# high_start.net
KiCad netlist of a schematic drawn in EAGLE
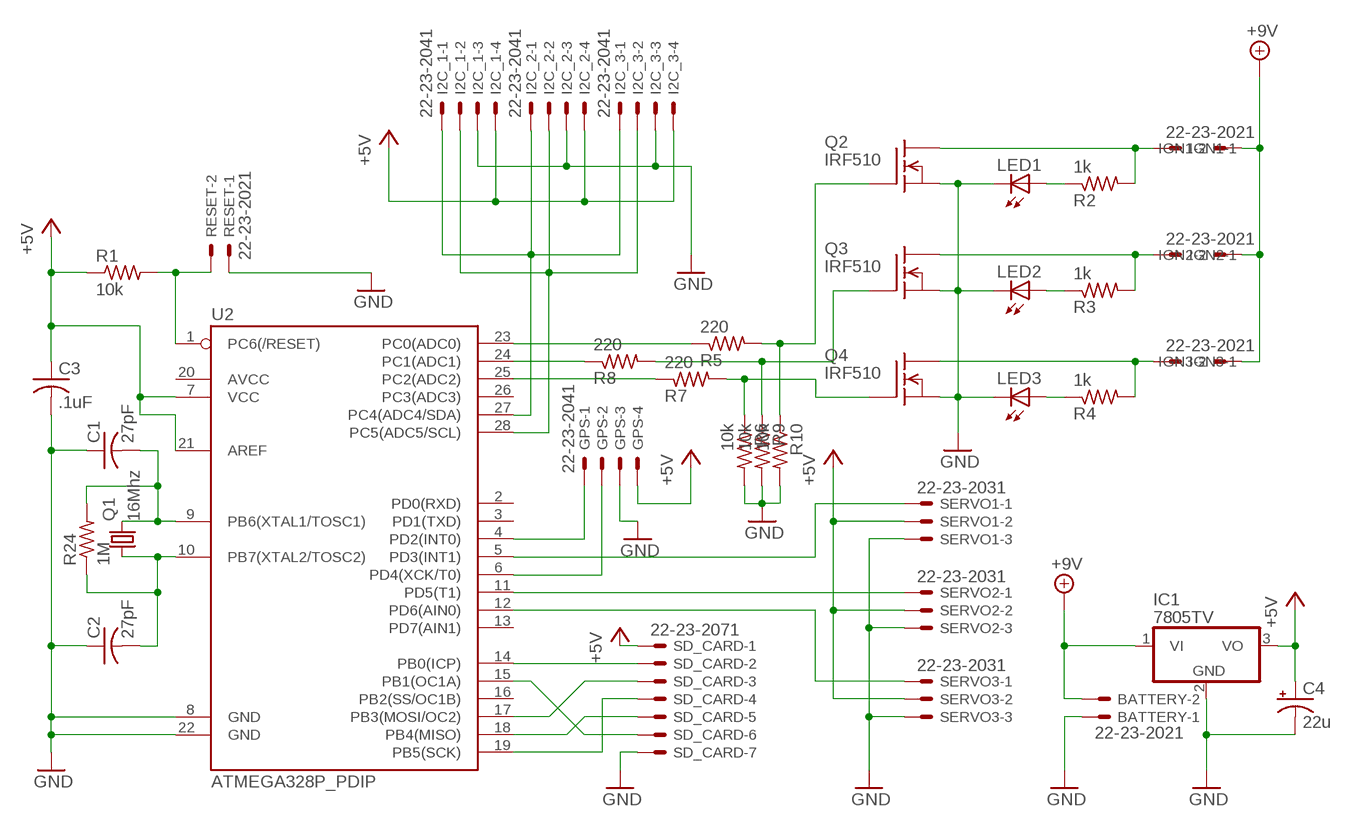
[diagram p0: schematic, sheet 1]

(export (version "E")
  (design (tool "Eeschema 10.0.6"))
  (components
    (comp (ref "BATTERY")
      (value "22-23-2021")
      (footprint "eagle-import:22-23-2021")
      (fields (field (name "MF") "MOLEX"))
      (libsource (lib "eagle-import") (part "22-23-2021"))
    )
    (comp (ref "C1")
      (value "27pF")
      (footprint "eagle-import:C025-040X050")
      (libsource (lib "eagle-import") (part "C-US025-040X050"))
    )
    (comp (ref "C2")
      (value "27pF")
      (footprint "eagle-import:C025-040X050")
      (libsource (lib "eagle-import") (part "C-US025-040X050"))
    )
    (comp (ref "C3")
      (value ".1uF")
      (footprint "eagle-import:C025-030X050")
      (libsource (lib "eagle-import") (part "C-US025-030X050"))
    )
    (comp (ref "C4")
      (value "22u")
      (footprint "eagle-import:B45181A")
      (libsource (lib "eagle-import") (part "CPOL-USB45181A"))
    )
    (comp (ref "GPS")
      (value "22-23-2041")
      (footprint "eagle-import:22-23-2041")
      (fields (field (name "MF") "MOLEX"))
      (libsource (lib "eagle-import") (part "22-23-2041"))
    )
    (comp (ref "I2C_1")
      (value "22-23-2041")
      (footprint "eagle-import:22-23-2041")
      (fields (field (name "MF") "MOLEX"))
      (libsource (lib "eagle-import") (part "22-23-2041"))
    )
    (comp (ref "I2C_2")
      (value "22-23-2041")
      (footprint "eagle-import:22-23-2041")
      (fields (field (name "MF") "MOLEX"))
      (libsource (lib "eagle-import") (part "22-23-2041"))
    )
    (comp (ref "I2C_3")
      (value "22-23-2041")
      (footprint "eagle-import:22-23-2041")
      (fields (field (name "MF") "MOLEX"))
      (libsource (lib "eagle-import") (part "22-23-2041"))
    )
    (comp (ref "IC1")
      (value "7805TV")
      (footprint "eagle-import:TO220V")
      (libsource (lib "eagle-import") (part "78TV05"))
    )
    (comp (ref "IGN1")
      (value "22-23-2021")
      (footprint "eagle-import:22-23-2021")
      (fields (field (name "MF") "MOLEX"))
      (libsource (lib "eagle-import") (part "22-23-2021"))
    )
    (comp (ref "IGN2")
      (value "22-23-2021")
      (footprint "eagle-import:22-23-2021")
      (fields (field (name "MF") "MOLEX"))
      (libsource (lib "eagle-import") (part "22-23-2021"))
    )
    (comp (ref "IGN3")
      (value "22-23-2021")
      (footprint "eagle-import:22-23-2021")
      (fields (field (name "MF") "MOLEX"))
      (libsource (lib "eagle-import") (part "22-23-2021"))
    )
    (comp (ref "LED1")
      (value "LED5MM")
      (footprint "eagle-import:LED5MM")
      (libsource (lib "eagle-import") (part "LED5MM"))
    )
    (comp (ref "LED2")
      (value "LED5MM")
      (footprint "eagle-import:LED5MM")
      (libsource (lib "eagle-import") (part "LED5MM"))
    )
    (comp (ref "LED3")
      (value "LED5MM")
      (footprint "eagle-import:LED5MM")
      (libsource (lib "eagle-import") (part "LED5MM"))
    )
    (comp (ref "Q1")
      (value "16Mhz")
      (footprint "eagle-import:HC49_S")
      (libsource (lib "eagle-import") (part "CRYSTALHC49S"))
    )
    (comp (ref "Q2")
      (value "IRF510")
      (footprint "eagle-import:TO220")
      (libsource (lib "eagle-import") (part "IRF510"))
    )
    (comp (ref "Q3")
      (value "IRF510")
      (footprint "eagle-import:TO220")
      (libsource (lib "eagle-import") (part "IRF510"))
    )
    (comp (ref "Q4")
      (value "IRF510")
      (footprint "eagle-import:TO220")
      (libsource (lib "eagle-import") (part "IRF510"))
    )
    (comp (ref "R1")
      (value "10k")
      (footprint "eagle-import:0207_7")
      (libsource (lib "eagle-import") (part "R-US_0207/7"))
    )
    (comp (ref "R2")
      (value "1k")
      (footprint "eagle-import:0207_7")
      (libsource (lib "eagle-import") (part "R-US_0207/7"))
    )
    (comp (ref "R3")
      (value "1k")
      (footprint "eagle-import:0207_7")
      (libsource (lib "eagle-import") (part "R-US_0207/7"))
    )
    (comp (ref "R4")
      (value "1k")
      (footprint "eagle-import:0207_7")
      (libsource (lib "eagle-import") (part "R-US_0207/7"))
    )
    (comp (ref "R5")
      (value "220")
      (footprint "eagle-import:0207_7")
      (libsource (lib "eagle-import") (part "R-US_0207/7"))
    )
    (comp (ref "R6")
      (value "10k")
      (footprint "eagle-import:0207_5V")
      (libsource (lib "eagle-import") (part "R-US_0207/5V"))
    )
    (comp (ref "R7")
      (value "220")
      (footprint "eagle-import:0207_7")
      (libsource (lib "eagle-import") (part "R-US_0207/7"))
    )
    (comp (ref "R8")
      (value "220")
      (footprint "eagle-import:0207_7")
      (libsource (lib "eagle-import") (part "R-US_0207/7"))
    )
    (comp (ref "R9")
      (value "10k")
      (footprint "eagle-import:0207_5V")
      (libsource (lib "eagle-import") (part "R-US_0207/5V"))
    )
    (comp (ref "R10")
      (value "10k")
      (footprint "eagle-import:0207_5V")
      (libsource (lib "eagle-import") (part "R-US_0207/5V"))
    )
    (comp (ref "R24")
      (value "1M")
      (footprint "eagle-import:0207_7")
      (libsource (lib "eagle-import") (part "R-US_0207/7"))
    )
    (comp (ref "RESET")
      (value "22-23-2021")
      (footprint "eagle-import:22-23-2021")
      (fields (field (name "MF") "MOLEX"))
      (libsource (lib "eagle-import") (part "22-23-2021"))
    )
    (comp (ref "SD_CARD")
      (value "22-23-2071")
      (footprint "eagle-import:22-23-2071")
      (fields (field (name "MF") "MOLEX"))
      (libsource (lib "eagle-import") (part "22-23-2071"))
    )
    (comp (ref "SERVO1")
      (value "22-23-2031")
      (footprint "eagle-import:22-23-2031")
      (fields (field (name "MF") "MOLEX"))
      (libsource (lib "eagle-import") (part "22-23-2031"))
    )
    (comp (ref "SERVO2")
      (value "22-23-2031")
      (footprint "eagle-import:22-23-2031")
      (fields (field (name "MF") "MOLEX"))
      (libsource (lib "eagle-import") (part "22-23-2031"))
    )
    (comp (ref "SERVO3")
      (value "22-23-2031")
      (footprint "eagle-import:22-23-2031")
      (fields (field (name "MF") "MOLEX"))
      (libsource (lib "eagle-import") (part "22-23-2031"))
    )
    (comp (ref "U2")
      (value "ATMEGA328P_PDIP")
      (footprint "eagle-import:DIL28-3")
      (libsource (lib "eagle-import") (part "ATMEGA328P_PDIP"))
    )
  )
  (nets
    (net (code "1") (name "+5V") (class "Default")
      (node (ref "C3") (pin "1") (pinfunction "1_1") (pintype "passive"))
      (node (ref "C4") (pin "+") (pinfunction "+_+") (pintype "passive"))
      (node (ref "GPS") (pin "4") (pinfunction "S_4") (pintype "passive"))
      (node (ref "I2C_1") (pin "4") (pinfunction "S_4") (pintype "passive"))
      (node (ref "I2C_2") (pin "4") (pinfunction "S_4") (pintype "passive"))
      (node (ref "I2C_3") (pin "4") (pinfunction "S_4") (pintype "passive"))
      (node (ref "IC1") (pin "3") (pinfunction "VO_3") (pintype "passive"))
      (node (ref "R1") (pin "1") (pinfunction "1_1") (pintype "passive"))
      (node (ref "SD_CARD") (pin "1") (pinfunction "S_1") (pintype "passive"))
      (node (ref "SERVO1") (pin "2") (pinfunction "S_2") (pintype "passive"))
      (node (ref "SERVO2") (pin "2") (pinfunction "S_2") (pintype "passive"))
      (node (ref "SERVO3") (pin "2") (pinfunction "S_2") (pintype "passive"))
      (node (ref "U2") (pin "21") (pinfunction "AREF_21") (pintype "bidirectional"))
      (node (ref "U2") (pin "7") (pinfunction "VCC_7") (pintype "bidirectional"))
    )
    (net (code "2") (name "+9V") (class "Default")
      (node (ref "BATTERY") (pin "2") (pinfunction "S_2") (pintype "passive"))
      (node (ref "IC1") (pin "1") (pinfunction "VI_1") (pintype "input"))
      (node (ref "IGN1") (pin "2") (pinfunction "S_2") (pintype "passive"))
      (node (ref "IGN2") (pin "2") (pinfunction "S_2") (pintype "passive"))
      (node (ref "IGN3") (pin "2") (pinfunction "S_2") (pintype "passive"))
    )
    (net (code "3") (name "GND") (class "Default")
      (node (ref "BATTERY") (pin "1") (pinfunction "S_1") (pintype "passive"))
      (node (ref "C1") (pin "1") (pinfunction "1_1") (pintype "passive"))
      (node (ref "C2") (pin "1") (pinfunction "1_1") (pintype "passive"))
      (node (ref "C3") (pin "2") (pinfunction "2_2") (pintype "passive"))
      (node (ref "C4") (pin "-") (pinfunction "-_-") (pintype "passive"))
      (node (ref "GPS") (pin "3") (pinfunction "S_3") (pintype "passive"))
      (node (ref "I2C_1") (pin "3") (pinfunction "S_3") (pintype "passive"))
      (node (ref "I2C_2") (pin "3") (pinfunction "S_3") (pintype "passive"))
      (node (ref "I2C_3") (pin "3") (pinfunction "S_3") (pintype "passive"))
      (node (ref "IC1") (pin "2") (pinfunction "GND_2") (pintype "passive"))
      (node (ref "LED1") (pin "K") (pinfunction "C_K") (pintype "passive"))
      (node (ref "LED2") (pin "K") (pinfunction "C_K") (pintype "passive"))
      (node (ref "LED3") (pin "K") (pinfunction "C_K") (pintype "passive"))
      (node (ref "Q2") (pin "3") (pinfunction "S_3") (pintype "passive"))
      (node (ref "Q3") (pin "3") (pinfunction "S_3") (pintype "passive"))
      (node (ref "Q4") (pin "3") (pinfunction "S_3") (pintype "passive"))
      (node (ref "R10") (pin "2") (pinfunction "2_2") (pintype "passive"))
      (node (ref "R6") (pin "2") (pinfunction "2_2") (pintype "passive"))
      (node (ref "R9") (pin "2") (pinfunction "2_2") (pintype "passive"))
      (node (ref "RESET") (pin "1") (pinfunction "S_1") (pintype "passive"))
      (node (ref "SD_CARD") (pin "7") (pinfunction "S_7") (pintype "passive"))
      (node (ref "SERVO1") (pin "3") (pinfunction "S_3") (pintype "passive"))
      (node (ref "SERVO2") (pin "3") (pinfunction "S_3") (pintype "passive"))
      (node (ref "SERVO3") (pin "3") (pinfunction "S_3") (pintype "passive"))
      (node (ref "U2") (pin "22") (pinfunction "GND_22") (pintype "bidirectional"))
      (node (ref "U2") (pin "8") (pinfunction "GND_8") (pintype "bidirectional"))
    )
    (net (code "4") (name "Net-(GPSA-S)") (class "Default")
      (node (ref "GPS") (pin "1") (pinfunction "S_1") (pintype "passive"))
      (node (ref "U2") (pin "4") (pinfunction "PD2(INT0)_4") (pintype "bidirectional"))
    )
    (net (code "5") (name "Net-(GPSB-S)") (class "Default")
      (node (ref "GPS") (pin "2") (pinfunction "S_2") (pintype "passive"))
      (node (ref "U2") (pin "6") (pinfunction "PD4(XCK/T0)_6") (pintype "bidirectional"))
    )
    (net (code "6") (name "Net-(I2C_1A-S)") (class "Default")
      (node (ref "I2C_1") (pin "1") (pinfunction "S_1") (pintype "passive"))
      (node (ref "I2C_2") (pin "1") (pinfunction "S_1") (pintype "passive"))
      (node (ref "I2C_3") (pin "1") (pinfunction "S_1") (pintype "passive"))
      (node (ref "U2") (pin "27") (pinfunction "PC4(ADC4/SDA)_27") (pintype "bidirectional"))
    )
    (net (code "7") (name "Net-(I2C_1B-S)") (class "Default")
      (node (ref "I2C_1") (pin "2") (pinfunction "S_2") (pintype "passive"))
      (node (ref "I2C_2") (pin "2") (pinfunction "S_2") (pintype "passive"))
      (node (ref "I2C_3") (pin "2") (pinfunction "S_2") (pintype "passive"))
      (node (ref "U2") (pin "28") (pinfunction "PC5(ADC5/SCL)_28") (pintype "bidirectional"))
    )
    (net (code "8") (name "Net-(IGN1A-S)") (class "Default")
      (node (ref "IGN1") (pin "1") (pinfunction "S_1") (pintype "passive"))
      (node (ref "Q2") (pin "2") (pinfunction "D_2") (pintype "passive"))
      (node (ref "R2") (pin "2") (pinfunction "2_2") (pintype "passive"))
    )
    (net (code "9") (name "Net-(IGN2A-S)") (class "Default")
      (node (ref "IGN2") (pin "1") (pinfunction "S_1") (pintype "passive"))
      (node (ref "Q3") (pin "2") (pinfunction "D_2") (pintype "passive"))
      (node (ref "R3") (pin "2") (pinfunction "2_2") (pintype "passive"))
    )
    (net (code "10") (name "Net-(IGN3A-S)") (class "Default")
      (node (ref "IGN3") (pin "1") (pinfunction "S_1") (pintype "passive"))
      (node (ref "Q4") (pin "2") (pinfunction "D_2") (pintype "passive"))
      (node (ref "R4") (pin "2") (pinfunction "2_2") (pintype "passive"))
    )
    (net (code "11") (name "Net-(LED1-PadA)") (class "Default")
      (node (ref "LED1") (pin "A") (pinfunction "A_A") (pintype "passive"))
      (node (ref "R2") (pin "1") (pinfunction "1_1") (pintype "passive"))
    )
    (net (code "12") (name "Net-(LED2-PadA)") (class "Default")
      (node (ref "LED2") (pin "A") (pinfunction "A_A") (pintype "passive"))
      (node (ref "R3") (pin "1") (pinfunction "1_1") (pintype "passive"))
    )
    (net (code "13") (name "Net-(LED3-PadA)") (class "Default")
      (node (ref "LED3") (pin "A") (pinfunction "A_A") (pintype "passive"))
      (node (ref "R4") (pin "1") (pinfunction "1_1") (pintype "passive"))
    )
    (net (code "14") (name "Net-(Q2-G)") (class "Default")
      (node (ref "Q2") (pin "1") (pinfunction "G_1") (pintype "passive"))
      (node (ref "R10") (pin "1") (pinfunction "1_1") (pintype "passive"))
      (node (ref "R5") (pin "2") (pinfunction "2_2") (pintype "passive"))
    )
    (net (code "15") (name "Net-(Q3-G)") (class "Default")
      (node (ref "Q3") (pin "1") (pinfunction "G_1") (pintype "passive"))
      (node (ref "R8") (pin "2") (pinfunction "2_2") (pintype "passive"))
      (node (ref "R9") (pin "1") (pinfunction "1_1") (pintype "passive"))
    )
    (net (code "16") (name "Net-(Q4-G)") (class "Default")
      (node (ref "Q4") (pin "1") (pinfunction "G_1") (pintype "passive"))
      (node (ref "R6") (pin "1") (pinfunction "1_1") (pintype "passive"))
      (node (ref "R7") (pin "2") (pinfunction "2_2") (pintype "passive"))
    )
    (net (code "17") (name "Net-(RESETB-S)") (class "Default")
      (node (ref "R1") (pin "2") (pinfunction "2_2") (pintype "passive"))
      (node (ref "RESET") (pin "2") (pinfunction "S_2") (pintype "passive"))
      (node (ref "U2") (pin "1") (pinfunction "PC6(/RESET)_1") (pintype "bidirectional"))
    )
    (net (code "18") (name "Net-(SD_CARDB-S)") (class "Default")
      (node (ref "SD_CARD") (pin "2") (pinfunction "S_2") (pintype "passive"))
      (node (ref "U2") (pin "14") (pinfunction "PB0(ICP)_14") (pintype "bidirectional"))
    )
    (net (code "19") (name "Net-(SD_CARDC-S)") (class "Default")
      (node (ref "SD_CARD") (pin "3") (pinfunction "S_3") (pintype "passive"))
      (node (ref "U2") (pin "17") (pinfunction "PB3(MOSI/OC2)_17") (pintype "bidirectional"))
    )
    (net (code "20") (name "Net-(SD_CARDD-S)") (class "Default")
      (node (ref "SD_CARD") (pin "4") (pinfunction "S_4") (pintype "passive"))
      (node (ref "U2") (pin "19") (pinfunction "PB5(SCK)_19") (pintype "bidirectional"))
    )
    (net (code "21") (name "Net-(SD_CARDE-S)") (class "Default")
      (node (ref "SD_CARD") (pin "5") (pinfunction "S_5") (pintype "passive"))
      (node (ref "U2") (pin "18") (pinfunction "PB4(MISO)_18") (pintype "bidirectional"))
    )
    (net (code "22") (name "Net-(SD_CARDF-S)") (class "Default")
      (node (ref "SD_CARD") (pin "6") (pinfunction "S_6") (pintype "passive"))
      (node (ref "U2") (pin "15") (pinfunction "PB1(OC1A)_15") (pintype "bidirectional"))
    )
    (net (code "23") (name "Net-(SERVO1A-S)") (class "Default")
      (node (ref "SERVO1") (pin "1") (pinfunction "S_1") (pintype "passive"))
      (node (ref "U2") (pin "5") (pinfunction "PD3(INT1)_5") (pintype "bidirectional"))
    )
    (net (code "24") (name "Net-(SERVO2A-S)") (class "Default")
      (node (ref "SERVO2") (pin "1") (pinfunction "S_1") (pintype "passive"))
      (node (ref "U2") (pin "11") (pinfunction "PD5(T1)_11") (pintype "bidirectional"))
    )
    (net (code "25") (name "Net-(SERVO3A-S)") (class "Default")
      (node (ref "SERVO3") (pin "1") (pinfunction "S_1") (pintype "passive"))
      (node (ref "U2") (pin "12") (pinfunction "PD6(AIN0)_12") (pintype "bidirectional"))
    )
    (net (code "26") (name "Net-(U2-PB6(XTAL1{slash}TOSC1))") (class "Default")
      (node (ref "C1") (pin "2") (pinfunction "2_2") (pintype "passive"))
      (node (ref "Q1") (pin "2") (pinfunction "2_2") (pintype "passive"))
      (node (ref "R24") (pin "2") (pinfunction "2_2") (pintype "passive"))
      (node (ref "U2") (pin "9") (pinfunction "PB6(XTAL1/TOSC1)_9") (pintype "bidirectional"))
    )
    (net (code "27") (name "Net-(U2-PB7(XTAL2{slash}TOSC2))") (class "Default")
      (node (ref "C2") (pin "2") (pinfunction "2_2") (pintype "passive"))
      (node (ref "Q1") (pin "1") (pinfunction "1_1") (pintype "passive"))
      (node (ref "R24") (pin "1") (pinfunction "1_1") (pintype "passive"))
      (node (ref "U2") (pin "10") (pinfunction "PB7(XTAL2/TOSC2)_10") (pintype "bidirectional"))
    )
    (net (code "28") (name "Net-(U2-PC0(ADC0))") (class "Default")
      (node (ref "R5") (pin "1") (pinfunction "1_1") (pintype "passive"))
      (node (ref "U2") (pin "23") (pinfunction "PC0(ADC0)_23") (pintype "bidirectional"))
    )
    (net (code "29") (name "Net-(U2-PC1(ADC1))") (class "Default")
      (node (ref "R8") (pin "1") (pinfunction "1_1") (pintype "passive"))
      (node (ref "U2") (pin "24") (pinfunction "PC1(ADC1)_24") (pintype "bidirectional"))
    )
    (net (code "30") (name "Net-(U2-PC2(ADC2))") (class "Default")
      (node (ref "R7") (pin "1") (pinfunction "1_1") (pintype "passive"))
      (node (ref "U2") (pin "25") (pinfunction "PC2(ADC2)_25") (pintype "bidirectional"))
    )
    (net (code "31") (name "unconnected-(U2-AVCC-Pad20)") (class "Default")
      (node (ref "U2") (pin "20") (pinfunction "AVCC_20") (pintype "bidirectional"))
    )
    (net (code "32") (name "unconnected-(U2-PB2(SS{slash}OC1B)-Pad16)") (class "Default")
      (node (ref "U2") (pin "16") (pinfunction "PB2(SS/OC1B)_16") (pintype "bidirectional"))
    )
    (net (code "33") (name "unconnected-(U2-PC3(ADC3)-Pad26)") (class "Default")
      (node (ref "U2") (pin "26") (pinfunction "PC3(ADC3)_26") (pintype "bidirectional"))
    )
    (net (code "34") (name "unconnected-(U2-PD0(RXD)-Pad2)") (class "Default")
      (node (ref "U2") (pin "2") (pinfunction "PD0(RXD)_2") (pintype "bidirectional"))
    )
    (net (code "35") (name "unconnected-(U2-PD1(TXD)-Pad3)") (class "Default")
      (node (ref "U2") (pin "3") (pinfunction "PD1(TXD)_3") (pintype "bidirectional"))
    )
    (net (code "36") (name "unconnected-(U2-PD7(AIN1)-Pad13)") (class "Default")
      (node (ref "U2") (pin "13") (pinfunction "PD7(AIN1)_13") (pintype "bidirectional"))
    )
  )
)
